# Tray2_Power_RedundantReg.net
KiCad netlist of a schematic drawn in Altium Designer
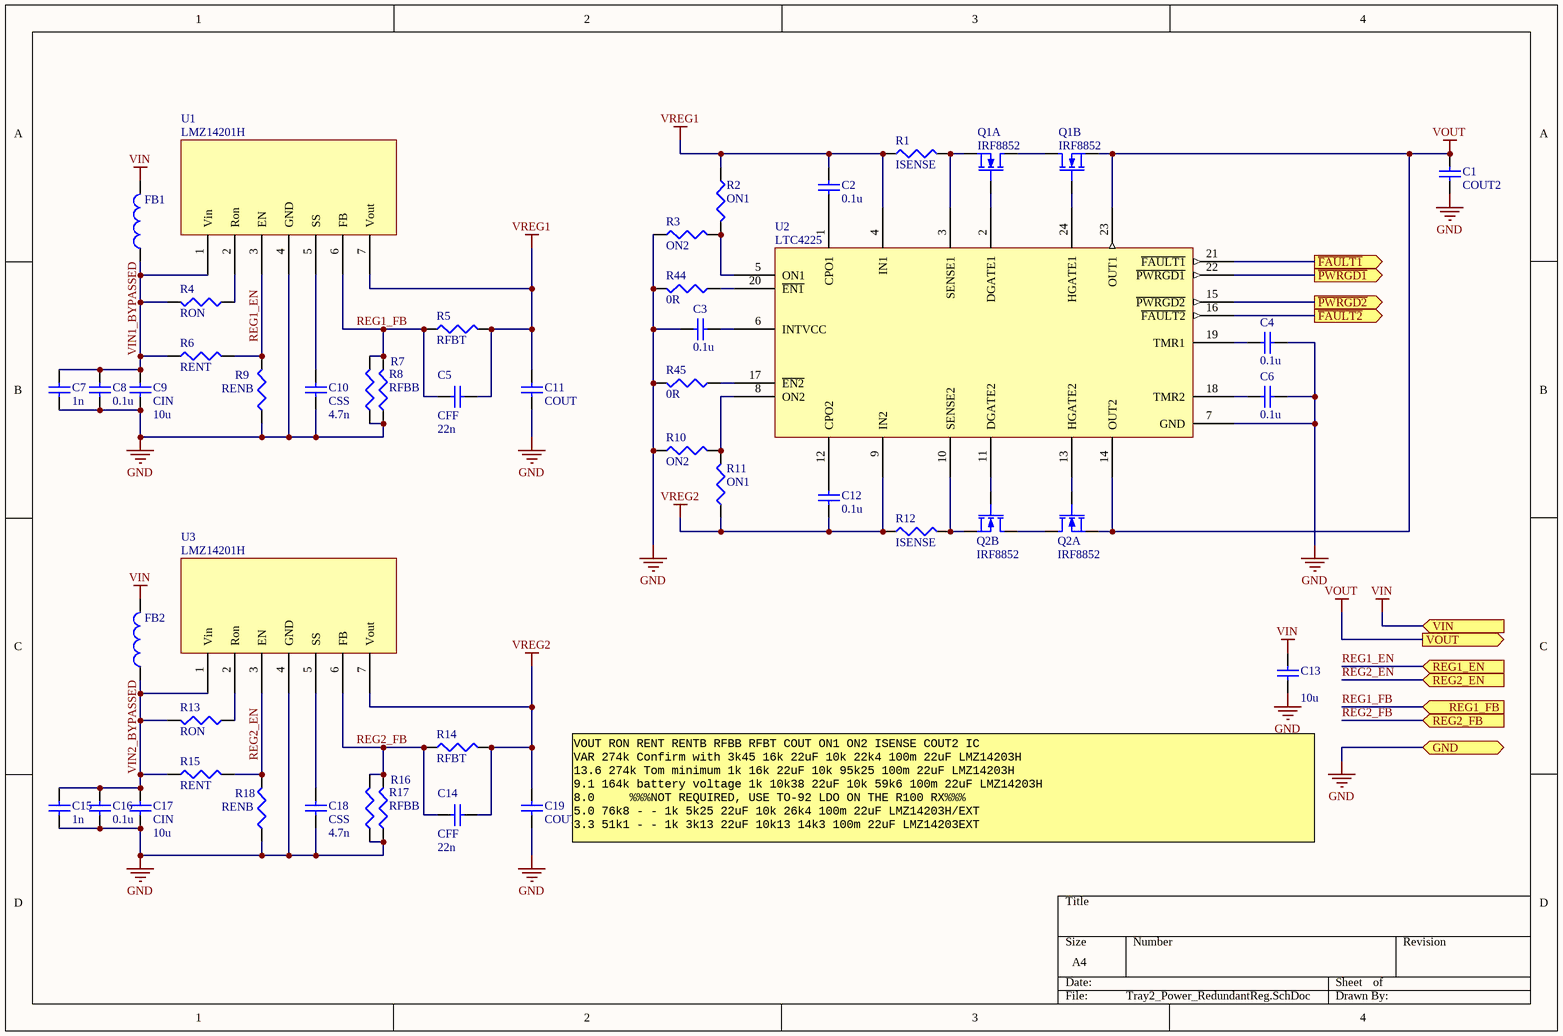
[diagram p0: Tray2_Power_RedundantReg.SchDoc]

(export (version "E")
  (design (tool "Eeschema 10.0.6"))
  (components
    (comp (ref "C1")
      (value "COUT2")
      (footprint "R1210M")
      (description "Capacitor")
      (fields (field (name "PUBLISHER") "Altium Limited"))
      (libsource (lib "Miscellaneous Devices") (part "Cap"))
    )
    (comp (ref "C2")
      (value "0.1u")
      (footprint "R0805M")
      (description "Capacitor")
      (fields (field (name "PUBLISHER") "Altium Limited"))
      (libsource (lib "Miscellaneous Devices") (part "Cap"))
    )
    (comp (ref "C3")
      (value "0.1u")
      (footprint "R0805M")
      (description "Capacitor")
      (fields (field (name "PUBLISHER") "Altium Limited"))
      (libsource (lib "Miscellaneous Devices") (part "Cap"))
    )
    (comp (ref "C4")
      (value "0.1u")
      (footprint "R0805M")
      (description "Capacitor")
      (fields (field (name "PUBLISHER") "Altium Limited"))
      (libsource (lib "Miscellaneous Devices") (part "Cap"))
    )
    (comp (ref "C5")
      (value "CFF")
      (footprint "R0805M")
      (description "Capacitor")
      (fields (field (name "ALTIUM_VALUE") "22n") (field (name "PUBLISHER") "Altium Limited"))
      (libsource (lib "Miscellaneous Devices") (part "Cap"))
    )
    (comp (ref "C6")
      (value "0.1u")
      (footprint "R0805M")
      (description "Capacitor")
      (fields (field (name "PUBLISHER") "Altium Limited"))
      (libsource (lib "Miscellaneous Devices") (part "Cap"))
    )
    (comp (ref "C7")
      (value "1n")
      (footprint "R0805M")
      (description "Capacitor")
      (fields (field (name "Comment") "CIN") (field (name "PUBLISHER") "Altium Limited"))
      (libsource (lib "Miscellaneous Devices") (part "Cap"))
    )
    (comp (ref "C8")
      (value "0.1u")
      (footprint "R0805M")
      (description "Capacitor")
      (fields (field (name "Comment") "CIN") (field (name "PUBLISHER") "Altium Limited"))
      (libsource (lib "Miscellaneous Devices") (part "Cap"))
    )
    (comp (ref "C9")
      (value "CIN")
      (footprint "R1210M")
      (description "Capacitor")
      (fields (field (name "ALTIUM_VALUE") "10u") (field (name "PUBLISHER") "Altium Limited"))
      (libsource (lib "Miscellaneous Devices") (part "Cap"))
    )
    (comp (ref "C10")
      (value "CSS")
      (footprint "R0805M")
      (description "Capacitor")
      (fields (field (name "ALTIUM_VALUE") "4.7n") (field (name "PUBLISHER") "Altium Limited"))
      (libsource (lib "Miscellaneous Devices") (part "Cap"))
    )
    (comp (ref "C11")
      (value "COUT")
      (footprint "R1210M")
      (description "Capacitor")
      (fields (field (name "PUBLISHER") "Altium Limited"))
      (libsource (lib "Miscellaneous Devices") (part "Cap"))
    )
    (comp (ref "C12")
      (value "0.1u")
      (footprint "R0805M")
      (description "Capacitor")
      (fields (field (name "PUBLISHER") "Altium Limited"))
      (libsource (lib "Miscellaneous Devices") (part "Cap"))
    )
    (comp (ref "C13")
      (value "10u")
      (footprint "R1210M")
      (description "Capacitor")
      (fields (field (name "PUBLISHER") "Altium Limited"))
      (libsource (lib "Miscellaneous Devices") (part "Cap"))
    )
    (comp (ref "C14")
      (value "CFF")
      (footprint "R0805M")
      (description "Capacitor")
      (fields (field (name "ALTIUM_VALUE") "22n") (field (name "PUBLISHER") "Altium Limited"))
      (libsource (lib "Miscellaneous Devices") (part "Cap"))
    )
    (comp (ref "C15")
      (value "1n")
      (footprint "R0805M")
      (description "Capacitor")
      (fields (field (name "Comment") "CIN") (field (name "PUBLISHER") "Altium Limited"))
      (libsource (lib "Miscellaneous Devices") (part "Cap"))
    )
    (comp (ref "C16")
      (value "0.1u")
      (footprint "R0805M")
      (description "Capacitor")
      (fields (field (name "Comment") "CIN") (field (name "PUBLISHER") "Altium Limited"))
      (libsource (lib "Miscellaneous Devices") (part "Cap"))
    )
    (comp (ref "C17")
      (value "CIN")
      (footprint "R1210M")
      (description "Capacitor")
      (fields (field (name "ALTIUM_VALUE") "10u") (field (name "PUBLISHER") "Altium Limited"))
      (libsource (lib "Miscellaneous Devices") (part "Cap"))
    )
    (comp (ref "C18")
      (value "CSS")
      (footprint "R0805M")
      (description "Capacitor")
      (fields (field (name "ALTIUM_VALUE") "4.7n") (field (name "PUBLISHER") "Altium Limited"))
      (libsource (lib "Miscellaneous Devices") (part "Cap"))
    )
    (comp (ref "C19")
      (value "COUT")
      (footprint "R1210M")
      (description "Capacitor")
      (fields (field (name "PUBLISHER") "Altium Limited"))
      (libsource (lib "Miscellaneous Devices") (part "Cap"))
    )
    (comp (ref "FB1")
      (value "~")
      (footprint "R0805M")
      (description "Inductor")
      (fields (field (name "PUBLISHER") "Altium Limited"))
      (libsource (lib "Miscellaneous Devices") (part "Inductor"))
    )
    (comp (ref "FB2")
      (value "~")
      (footprint "R0805M")
      (description "Inductor")
      (fields (field (name "PUBLISHER") "Altium Limited"))
      (libsource (lib "Miscellaneous Devices") (part "Inductor"))
    )
    (comp (ref "Q1")
      (value "IRF8852")
      (footprint "TSSOP8")
      (description "N-Channel MOSFET")
      (fields (field (name "PUBLISHER") "Altium Limited"))
      (libsource (lib "SchLib") (part "IRF8852"))
    )
    (comp (ref "Q2")
      (value "IRF8852")
      (footprint "TSSOP8")
      (description "N-Channel MOSFET")
      (fields (field (name "PUBLISHER") "Altium Limited"))
      (libsource (lib "SchLib") (part "IRF8852"))
    )
    (comp (ref "R1")
      (value "ISENSE")
      (footprint "R0805M")
      (description "Resistor")
      (fields (field (name "PUBLISHER") "Altium Limited"))
      (libsource (lib "Miscellaneous Devices") (part "Res3"))
    )
    (comp (ref "R2")
      (value "ON1")
      (footprint "R0805M")
      (description "Resistor")
      (fields (field (name "PUBLISHER") "Altium Limited"))
      (libsource (lib "Miscellaneous Devices") (part "Res3"))
    )
    (comp (ref "R3")
      (value "ON2")
      (footprint "R0805M")
      (description "Resistor")
      (fields (field (name "PUBLISHER") "Altium Limited"))
      (libsource (lib "Miscellaneous Devices") (part "Res3"))
    )
    (comp (ref "R4")
      (value "RON")
      (footprint "R0805M")
      (description "Resistor")
      (fields (field (name "PUBLISHER") "Altium Limited"))
      (libsource (lib "Miscellaneous Devices") (part "Res3"))
    )
    (comp (ref "R5")
      (value "RFBT")
      (footprint "R0805M")
      (description "Resistor")
      (fields (field (name "PUBLISHER") "Altium Limited"))
      (libsource (lib "Miscellaneous Devices") (part "Res3"))
    )
    (comp (ref "R6")
      (value "RENT")
      (footprint "R0805M")
      (description "Resistor")
      (fields (field (name "PUBLISHER") "Altium Limited"))
      (libsource (lib "Miscellaneous Devices") (part "Res3"))
    )
    (comp (ref "R7")
      (value "RFBB")
      (footprint "R0805M")
      (description "Resistor")
      (fields (field (name "PUBLISHER") "Altium Limited"))
      (libsource (lib "Miscellaneous Devices") (part "Res3"))
    )
    (comp (ref "R8")
      (value "RFBB")
      (footprint "R0805M")
      (description "Resistor")
      (fields (field (name "PUBLISHER") "Altium Limited"))
      (libsource (lib "Miscellaneous Devices") (part "Res3"))
    )
    (comp (ref "R9")
      (value "RENB")
      (footprint "R0805M")
      (description "Resistor")
      (fields (field (name "PUBLISHER") "Altium Limited"))
      (libsource (lib "Miscellaneous Devices") (part "Res3"))
    )
    (comp (ref "R10")
      (value "ON2")
      (footprint "R0805M")
      (description "Resistor")
      (fields (field (name "PUBLISHER") "Altium Limited"))
      (libsource (lib "Miscellaneous Devices") (part "Res3"))
    )
    (comp (ref "R11")
      (value "ON1")
      (footprint "R0805M")
      (description "Resistor")
      (fields (field (name "PUBLISHER") "Altium Limited"))
      (libsource (lib "Miscellaneous Devices") (part "Res3"))
    )
    (comp (ref "R12")
      (value "ISENSE")
      (footprint "R0805M")
      (description "Resistor")
      (fields (field (name "PUBLISHER") "Altium Limited"))
      (libsource (lib "Miscellaneous Devices") (part "Res3"))
    )
    (comp (ref "R13")
      (value "RON")
      (footprint "R0805M")
      (description "Resistor")
      (fields (field (name "PUBLISHER") "Altium Limited"))
      (libsource (lib "Miscellaneous Devices") (part "Res3"))
    )
    (comp (ref "R14")
      (value "RFBT")
      (footprint "R0805M")
      (description "Resistor")
      (fields (field (name "PUBLISHER") "Altium Limited"))
      (libsource (lib "Miscellaneous Devices") (part "Res3"))
    )
    (comp (ref "R15")
      (value "RENT")
      (footprint "R0805M")
      (description "Resistor")
      (fields (field (name "PUBLISHER") "Altium Limited"))
      (libsource (lib "Miscellaneous Devices") (part "Res3"))
    )
    (comp (ref "R16")
      (value "RFBB")
      (footprint "R0805M")
      (description "Resistor")
      (fields (field (name "PUBLISHER") "Altium Limited"))
      (libsource (lib "Miscellaneous Devices") (part "Res3"))
    )
    (comp (ref "R17")
      (value "RFBB")
      (footprint "R0805M")
      (description "Resistor")
      (fields (field (name "PUBLISHER") "Altium Limited"))
      (libsource (lib "Miscellaneous Devices") (part "Res3"))
    )
    (comp (ref "R18")
      (value "RENB")
      (footprint "R0805M")
      (description "Resistor")
      (fields (field (name "PUBLISHER") "Altium Limited"))
      (libsource (lib "Miscellaneous Devices") (part "Res3"))
    )
    (comp (ref "R44")
      (value "0R")
      (footprint "R0805M")
      (description "Resistor")
      (fields (field (name "PUBLISHER") "Altium Limited"))
      (libsource (lib "Miscellaneous Devices") (part "Res3"))
    )
    (comp (ref "R45")
      (value "0R")
      (footprint "R0805M")
      (description "Resistor")
      (fields (field (name "PUBLISHER") "Altium Limited"))
      (libsource (lib "Miscellaneous Devices") (part "Res3"))
    )
    (comp (ref "U1")
      (value "LMZ14201H")
      (footprint "TO-PMOD-7")
      (description "1A SIMPLE SWITCHER® Power Module for High Output  Voltage")
      (libsource (lib "SchLib") (part "LMZ14201H"))
    )
    (comp (ref "U2")
      (value "LTC4225")
      (footprint "SSOP24")
      (description "Dual Ideal Diode and  Hot Swap Controller")
      (libsource (lib "SchLib") (part "LTC4225"))
    )
    (comp (ref "U3")
      (value "LMZ14201H")
      (footprint "TO-PMOD-7")
      (description "1A SIMPLE SWITCHER® Power Module for High Output  Voltage")
      (libsource (lib "SchLib") (part "LMZ14201H"))
    )
  )
  (nets
    (net (code "1") (name "/REG1_EN") (class "Default")
      (node (ref "R6") (pin "2") (pinfunction "2_2") (pintype "passive"))
      (node (ref "R9") (pin "1") (pinfunction "1_1") (pintype "passive"))
      (node (ref "U1") (pin "3") (pinfunction "EN_3") (pintype "passive"))
    )
    (net (code "2") (name "/REG1_FB") (class "Default")
      (node (ref "C5") (pin "1") (pinfunction "1_1") (pintype "passive"))
      (node (ref "R5") (pin "1") (pinfunction "1_1") (pintype "passive"))
      (node (ref "R7") (pin "2") (pinfunction "2_2") (pintype "passive"))
      (node (ref "R8") (pin "2") (pinfunction "2_2") (pintype "passive"))
      (node (ref "U1") (pin "6") (pinfunction "FB_6") (pintype "passive"))
    )
    (net (code "3") (name "/REG2_EN") (class "Default")
      (node (ref "R15") (pin "2") (pinfunction "2_2") (pintype "passive"))
      (node (ref "R18") (pin "1") (pinfunction "1_1") (pintype "passive"))
      (node (ref "U3") (pin "3") (pinfunction "EN_3") (pintype "passive"))
    )
    (net (code "4") (name "/REG2_FB") (class "Default")
      (node (ref "C14") (pin "1") (pinfunction "1_1") (pintype "passive"))
      (node (ref "R14") (pin "1") (pinfunction "1_1") (pintype "passive"))
      (node (ref "R16") (pin "2") (pinfunction "2_2") (pintype "passive"))
      (node (ref "R17") (pin "2") (pinfunction "2_2") (pintype "passive"))
      (node (ref "U3") (pin "6") (pinfunction "FB_6") (pintype "passive"))
    )
    (net (code "5") (name "/VIN1_BYPASSED") (class "Default")
      (node (ref "C7") (pin "2") (pinfunction "2_2") (pintype "passive"))
      (node (ref "C8") (pin "2") (pinfunction "2_2") (pintype "passive"))
      (node (ref "C9") (pin "1") (pinfunction "1_1") (pintype "passive"))
      (node (ref "FB1") (pin "1") (pinfunction "1_1") (pintype "passive"))
      (node (ref "R4") (pin "2") (pinfunction "2_2") (pintype "passive"))
      (node (ref "R6") (pin "1") (pinfunction "1_1") (pintype "passive"))
      (node (ref "U1") (pin "1") (pinfunction "Vin_1") (pintype "passive"))
    )
    (net (code "6") (name "/VIN2_BYPASSED") (class "Default")
      (node (ref "C15") (pin "2") (pinfunction "2_2") (pintype "passive"))
      (node (ref "C16") (pin "2") (pinfunction "2_2") (pintype "passive"))
      (node (ref "C17") (pin "1") (pinfunction "1_1") (pintype "passive"))
      (node (ref "FB2") (pin "1") (pinfunction "1_1") (pintype "passive"))
      (node (ref "R13") (pin "2") (pinfunction "2_2") (pintype "passive"))
      (node (ref "R15") (pin "1") (pinfunction "1_1") (pintype "passive"))
      (node (ref "U3") (pin "1") (pinfunction "Vin_1") (pintype "passive"))
    )
    (net (code "7") (name "/~{FAULT1}") (class "Default")
      (node (ref "U2") (pin "21") (pinfunction "~{FAULT1}_21") (pintype "output"))
    )
    (net (code "8") (name "/~{FAULT2}") (class "Default")
      (node (ref "U2") (pin "16") (pinfunction "~{FAULT2}_16") (pintype "output"))
    )
    (net (code "9") (name "/~{PWRGD1}") (class "Default")
      (node (ref "U2") (pin "22") (pinfunction "~{PWRGD1}_22") (pintype "output"))
    )
    (net (code "10") (name "/~{PWRGD2}") (class "Default")
      (node (ref "U2") (pin "15") (pinfunction "~{PWRGD2}_15") (pintype "output"))
    )
    (net (code "11") (name "GND") (class "Default")
      (node (ref "C1") (pin "1") (pinfunction "1_1") (pintype "passive"))
      (node (ref "C10") (pin "2") (pinfunction "2_2") (pintype "passive"))
      (node (ref "C11") (pin "1") (pinfunction "1_1") (pintype "passive"))
      (node (ref "C13") (pin "2") (pinfunction "2_2") (pintype "passive"))
      (node (ref "C15") (pin "1") (pinfunction "1_1") (pintype "passive"))
      (node (ref "C16") (pin "1") (pinfunction "1_1") (pintype "passive"))
      (node (ref "C17") (pin "2") (pinfunction "2_2") (pintype "passive"))
      (node (ref "C18") (pin "2") (pinfunction "2_2") (pintype "passive"))
      (node (ref "C19") (pin "1") (pinfunction "1_1") (pintype "passive"))
      (node (ref "C3") (pin "2") (pinfunction "2_2") (pintype "passive"))
      (node (ref "C4") (pin "1") (pinfunction "1_1") (pintype "passive"))
      (node (ref "C6") (pin "1") (pinfunction "1_1") (pintype "passive"))
      (node (ref "C7") (pin "1") (pinfunction "1_1") (pintype "passive"))
      (node (ref "C8") (pin "1") (pinfunction "1_1") (pintype "passive"))
      (node (ref "C9") (pin "2") (pinfunction "2_2") (pintype "passive"))
      (node (ref "R10") (pin "1") (pinfunction "1_1") (pintype "passive"))
      (node (ref "R16") (pin "1") (pinfunction "1_1") (pintype "passive"))
      (node (ref "R17") (pin "1") (pinfunction "1_1") (pintype "passive"))
      (node (ref "R18") (pin "2") (pinfunction "2_2") (pintype "passive"))
      (node (ref "R3") (pin "1") (pinfunction "1_1") (pintype "passive"))
      (node (ref "R44") (pin "2") (pinfunction "2_2") (pintype "passive"))
      (node (ref "R45") (pin "2") (pinfunction "2_2") (pintype "passive"))
      (node (ref "R7") (pin "1") (pinfunction "1_1") (pintype "passive"))
      (node (ref "R8") (pin "1") (pinfunction "1_1") (pintype "passive"))
      (node (ref "R9") (pin "2") (pinfunction "2_2") (pintype "passive"))
      (node (ref "U1") (pin "4") (pinfunction "GND_4") (pintype "passive"))
      (node (ref "U2") (pin "7") (pinfunction "GND_7") (pintype "passive"))
      (node (ref "U3") (pin "4") (pinfunction "GND_4") (pintype "passive"))
    )
    (net (code "12") (name "Net-(Q1A-D)") (class "Default")
      (node (ref "Q1") (pin "D1") (pinfunction "D_D1") (pintype "passive"))
      (node (ref "Q1") (pin "D2") (pinfunction "D_D2") (pintype "passive"))
    )
    (net (code "13") (name "Net-(Q1A-G)") (class "Default")
      (node (ref "Q1") (pin "G1") (pinfunction "G_G1") (pintype "passive"))
      (node (ref "U2") (pin "2") (pinfunction "DGATE1_2") (pintype "passive"))
    )
    (net (code "14") (name "Net-(Q1A-S)") (class "Default")
      (node (ref "Q1") (pin "S1") (pinfunction "S_S1") (pintype "passive"))
      (node (ref "R1") (pin "2") (pinfunction "2_2") (pintype "passive"))
      (node (ref "U2") (pin "3") (pinfunction "SENSE1_3") (pintype "passive"))
    )
    (net (code "15") (name "Net-(Q1B-G)") (class "Default")
      (node (ref "Q1") (pin "G2") (pinfunction "G_G2") (pintype "passive"))
      (node (ref "U2") (pin "24") (pinfunction "HGATE1_24") (pintype "passive"))
    )
    (net (code "16") (name "Net-(Q2A-D)") (class "Default")
      (node (ref "Q2") (pin "D1") (pinfunction "D_D1") (pintype "passive"))
      (node (ref "Q2") (pin "D2") (pinfunction "D_D2") (pintype "passive"))
    )
    (net (code "17") (name "Net-(Q2A-G)") (class "Default")
      (node (ref "Q2") (pin "G1") (pinfunction "G_G1") (pintype "passive"))
      (node (ref "U2") (pin "13") (pinfunction "HGATE2_13") (pintype "passive"))
    )
    (net (code "18") (name "Net-(Q2B-G)") (class "Default")
      (node (ref "Q2") (pin "G2") (pinfunction "G_G2") (pintype "passive"))
      (node (ref "U2") (pin "11") (pinfunction "DGATE2_11") (pintype "passive"))
    )
    (net (code "19") (name "Net-(Q2B-S)") (class "Default")
      (node (ref "Q2") (pin "S2") (pinfunction "S_S2") (pintype "passive"))
      (node (ref "R12") (pin "2") (pinfunction "2_2") (pintype "passive"))
      (node (ref "U2") (pin "10") (pinfunction "SENSE2_10") (pintype "passive"))
    )
    (net (code "20") (name "Net-(U1-Ron)") (class "Default")
      (node (ref "R4") (pin "1") (pinfunction "1_1") (pintype "passive"))
      (node (ref "U1") (pin "2") (pinfunction "Ron_2") (pintype "passive"))
    )
    (net (code "21") (name "Net-(U1-SS)") (class "Default")
      (node (ref "C10") (pin "1") (pinfunction "1_1") (pintype "passive"))
      (node (ref "U1") (pin "5") (pinfunction "SS_5") (pintype "passive"))
    )
    (net (code "22") (name "Net-(U2-CPO1)") (class "Default")
      (node (ref "C2") (pin "2") (pinfunction "2_2") (pintype "passive"))
      (node (ref "U2") (pin "1") (pinfunction "CPO1_1") (pintype "passive"))
    )
    (net (code "23") (name "Net-(U2-CPO2)") (class "Default")
      (node (ref "C12") (pin "1") (pinfunction "1_1") (pintype "passive"))
      (node (ref "U2") (pin "12") (pinfunction "CPO2_12") (pintype "passive"))
    )
    (net (code "24") (name "Net-(U2-INTVCC)") (class "Default")
      (node (ref "C3") (pin "1") (pinfunction "1_1") (pintype "passive"))
      (node (ref "U2") (pin "6") (pinfunction "INTVCC_6") (pintype "passive"))
    )
    (net (code "25") (name "Net-(U2-ON1)") (class "Default")
      (node (ref "R2") (pin "2") (pinfunction "2_2") (pintype "passive"))
      (node (ref "R3") (pin "2") (pinfunction "2_2") (pintype "passive"))
      (node (ref "U2") (pin "5") (pinfunction "ON1_5") (pintype "passive"))
    )
    (net (code "26") (name "Net-(U2-ON2)") (class "Default")
      (node (ref "R10") (pin "2") (pinfunction "2_2") (pintype "passive"))
      (node (ref "R11") (pin "2") (pinfunction "2_2") (pintype "passive"))
      (node (ref "U2") (pin "8") (pinfunction "ON2_8") (pintype "passive"))
    )
    (net (code "27") (name "Net-(U2-TMR1)") (class "Default")
      (node (ref "C4") (pin "2") (pinfunction "2_2") (pintype "passive"))
      (node (ref "U2") (pin "19") (pinfunction "TMR1_19") (pintype "passive"))
    )
    (net (code "28") (name "Net-(U2-TMR2)") (class "Default")
      (node (ref "C6") (pin "2") (pinfunction "2_2") (pintype "passive"))
      (node (ref "U2") (pin "18") (pinfunction "TMR2_18") (pintype "passive"))
    )
    (net (code "29") (name "Net-(U2-~{EN1})") (class "Default")
      (node (ref "R44") (pin "1") (pinfunction "1_1") (pintype "passive"))
      (node (ref "U2") (pin "20") (pinfunction "~{EN1}_20") (pintype "passive"))
    )
    (net (code "30") (name "Net-(U2-~{EN2})") (class "Default")
      (node (ref "R45") (pin "1") (pinfunction "1_1") (pintype "passive"))
      (node (ref "U2") (pin "17") (pinfunction "~{EN2}_17") (pintype "passive"))
    )
    (net (code "31") (name "Net-(U3-Ron)") (class "Default")
      (node (ref "R13") (pin "1") (pinfunction "1_1") (pintype "passive"))
      (node (ref "U3") (pin "2") (pinfunction "Ron_2") (pintype "passive"))
    )
    (net (code "32") (name "Net-(U3-SS)") (class "Default")
      (node (ref "C18") (pin "1") (pinfunction "1_1") (pintype "passive"))
      (node (ref "U3") (pin "5") (pinfunction "SS_5") (pintype "passive"))
    )
    (net (code "33") (name "VIN") (class "Default")
      (node (ref "C13") (pin "1") (pinfunction "1_1") (pintype "passive"))
      (node (ref "FB1") (pin "2") (pinfunction "2_2") (pintype "passive"))
      (node (ref "FB2") (pin "2") (pinfunction "2_2") (pintype "passive"))
    )
    (net (code "34") (name "VOUT") (class "Default")
      (node (ref "C1") (pin "2") (pinfunction "2_2") (pintype "passive"))
      (node (ref "Q1") (pin "S2") (pinfunction "S_S2") (pintype "passive"))
      (node (ref "Q2") (pin "S1") (pinfunction "S_S1") (pintype "passive"))
      (node (ref "U2") (pin "14") (pinfunction "OUT2_14") (pintype "passive"))
      (node (ref "U2") (pin "23") (pinfunction "OUT1_23") (pintype "output"))
    )
    (net (code "35") (name "VREG1") (class "Default")
      (node (ref "C11") (pin "2") (pinfunction "2_2") (pintype "passive"))
      (node (ref "C2") (pin "1") (pinfunction "1_1") (pintype "passive"))
      (node (ref "C5") (pin "2") (pinfunction "2_2") (pintype "passive"))
      (node (ref "R1") (pin "1") (pinfunction "1_1") (pintype "passive"))
      (node (ref "R2") (pin "1") (pinfunction "1_1") (pintype "passive"))
      (node (ref "R5") (pin "2") (pinfunction "2_2") (pintype "passive"))
      (node (ref "U1") (pin "7") (pinfunction "Vout_7") (pintype "passive"))
      (node (ref "U2") (pin "4") (pinfunction "IN1_4") (pintype "passive"))
    )
    (net (code "36") (name "VREG2") (class "Default")
      (node (ref "C12") (pin "2") (pinfunction "2_2") (pintype "passive"))
      (node (ref "C14") (pin "2") (pinfunction "2_2") (pintype "passive"))
      (node (ref "C19") (pin "2") (pinfunction "2_2") (pintype "passive"))
      (node (ref "R11") (pin "1") (pinfunction "1_1") (pintype "passive"))
      (node (ref "R12") (pin "1") (pinfunction "1_1") (pintype "passive"))
      (node (ref "R14") (pin "2") (pinfunction "2_2") (pintype "passive"))
      (node (ref "U2") (pin "9") (pinfunction "IN2_9") (pintype "passive"))
      (node (ref "U3") (pin "7") (pinfunction "Vout_7") (pintype "passive"))
    )
  )
)
